# T14_V2_METROKNOME.net
KiCad netlist of a schematic drawn in EAGLE
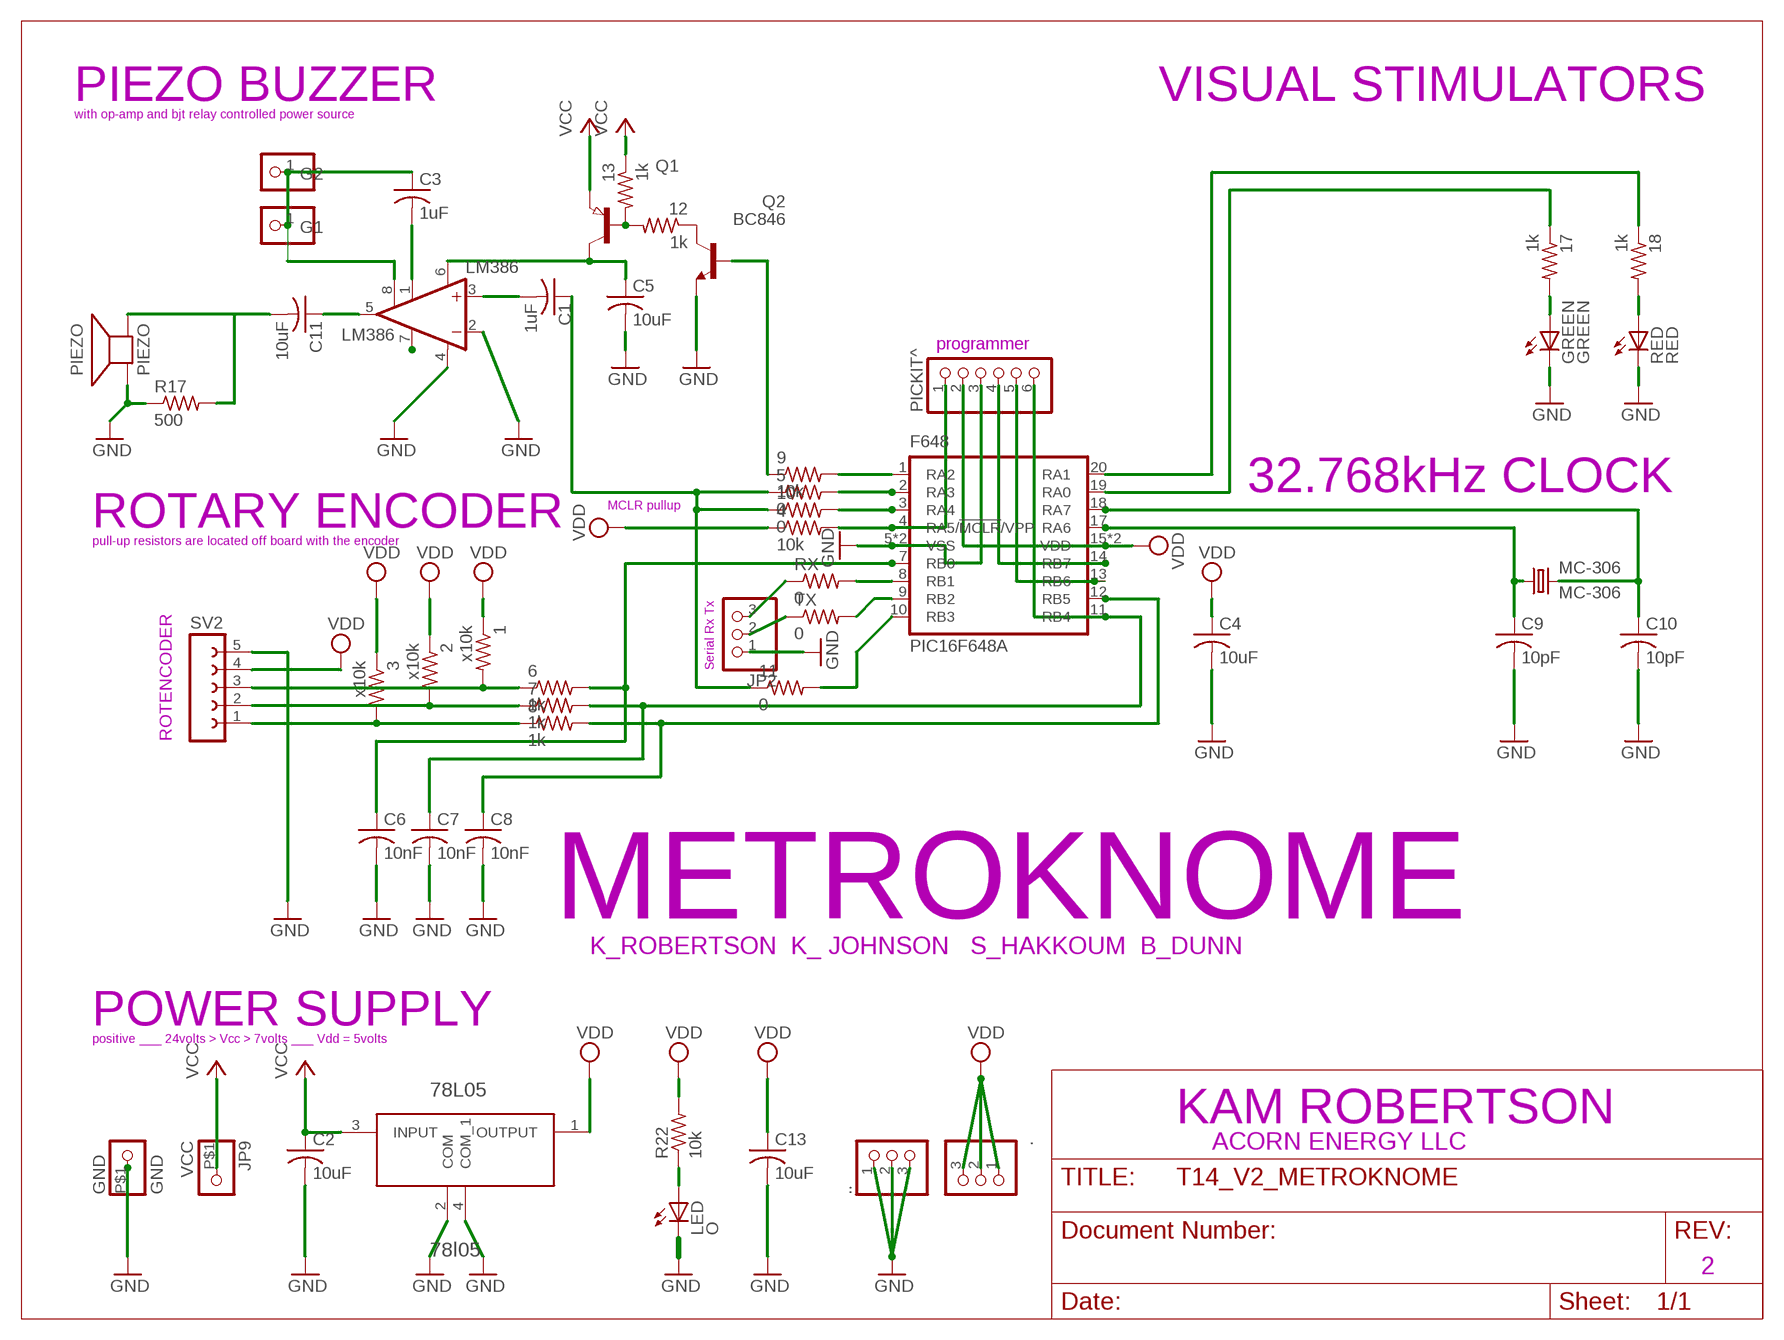
[diagram p0: schematic, sheet 1]

(export (version "E")
  (design (tool "Eeschema 10.0.6"))
  (components
    (comp (ref ".")
      (value "PINHD-1X3CB")
      (footprint "eagle-import:1X03-CLEANBIG")
      (libsource (lib "eagle-import") (part "PINHD-1X3CB"))
    )
    (comp (ref "..")
      (value "PINHD-1X3CB")
      (footprint "eagle-import:1X03-CLEANBIG")
      (libsource (lib "eagle-import") (part "PINHD-1X3CB"))
    )
    (comp (ref "1")
      (value "x10k")
      (footprint "eagle-import:R0603")
      (libsource (lib "eagle-import") (part "R-US_R0603"))
    )
    (comp (ref "2")
      (value "x10k")
      (footprint "eagle-import:R0603")
      (libsource (lib "eagle-import") (part "R-US_R0603"))
    )
    (comp (ref "3")
      (value "x10k")
      (footprint "eagle-import:R0603")
      (libsource (lib "eagle-import") (part "R-US_R0603"))
    )
    (comp (ref "4")
      (value "10k")
      (footprint "eagle-import:R1206")
      (libsource (lib "eagle-import") (part "R-US_R1206"))
    )
    (comp (ref "5")
      (value "0")
      (footprint "eagle-import:R0603")
      (libsource (lib "eagle-import") (part "R-US_R0603"))
    )
    (comp (ref "6")
      (value "1k")
      (footprint "eagle-import:R1206")
      (libsource (lib "eagle-import") (part "R-US_R1206"))
    )
    (comp (ref "7")
      (value "1k")
      (footprint "eagle-import:R1206")
      (libsource (lib "eagle-import") (part "R-US_R1206"))
    )
    (comp (ref "8")
      (value "1k")
      (footprint "eagle-import:R1206")
      (libsource (lib "eagle-import") (part "R-US_R1206"))
    )
    (comp (ref "9")
      (value "10k")
      (footprint "eagle-import:R1206")
      (libsource (lib "eagle-import") (part "R-US_R1206"))
    )
    (comp (ref "10")
      (value "0")
      (footprint "eagle-import:R0603")
      (libsource (lib "eagle-import") (part "R-US_R0603"))
    )
    (comp (ref "11")
      (value "0")
      (footprint "eagle-import:R1206")
      (libsource (lib "eagle-import") (part "R-US_R1206"))
    )
    (comp (ref "12")
      (value "1k")
      (footprint "eagle-import:R1206")
      (libsource (lib "eagle-import") (part "R-US_R1206"))
    )
    (comp (ref "13")
      (value "1k")
      (footprint "eagle-import:R1206")
      (libsource (lib "eagle-import") (part "R-US_R1206"))
    )
    (comp (ref "17")
      (value "1k")
      (footprint "eagle-import:R1206")
      (libsource (lib "eagle-import") (part "R-US_R1206"))
    )
    (comp (ref "18")
      (value "1k")
      (footprint "eagle-import:R1206")
      (libsource (lib "eagle-import") (part "R-US_R1206"))
    )
    (comp (ref "78L05")
      (value "78l05")
      (footprint "eagle-import:SOT150P400X160-4N")
      (fields (field (name "MPN") "UA78L05ACPKG3"))
      (libsource (lib "eagle-import") (part "UA78L05ACPKG3"))
    )
    (comp (ref "C1")
      (value "1uF")
      (footprint "eagle-import:C1210")
      (libsource (lib "eagle-import") (part "C-USC1210"))
    )
    (comp (ref "C2")
      (value "10uF")
      (footprint "eagle-import:C1210")
      (libsource (lib "eagle-import") (part "C-USC1210"))
    )
    (comp (ref "C3")
      (value "1uF")
      (footprint "eagle-import:C1210")
      (libsource (lib "eagle-import") (part "C-USC1210"))
    )
    (comp (ref "C4")
      (value "10uF")
      (footprint "eagle-import:C1210")
      (libsource (lib "eagle-import") (part "C-USC1210"))
    )
    (comp (ref "C5")
      (value "10uF")
      (footprint "eagle-import:C1210")
      (libsource (lib "eagle-import") (part "C-USC1210"))
    )
    (comp (ref "C6")
      (value "10nF")
      (footprint "eagle-import:C1210")
      (libsource (lib "eagle-import") (part "C-USC1210"))
    )
    (comp (ref "C7")
      (value "10nF")
      (footprint "eagle-import:C1210")
      (libsource (lib "eagle-import") (part "C-USC1210"))
    )
    (comp (ref "C8")
      (value "10nF")
      (footprint "eagle-import:C1210")
      (libsource (lib "eagle-import") (part "C-USC1210"))
    )
    (comp (ref "C9")
      (value "10pF")
      (footprint "eagle-import:C1210")
      (libsource (lib "eagle-import") (part "C-USC1210"))
    )
    (comp (ref "C10")
      (value "10pF")
      (footprint "eagle-import:C1210")
      (libsource (lib "eagle-import") (part "C-USC1210"))
    )
    (comp (ref "C11")
      (value "10uF")
      (footprint "eagle-import:C1210")
      (libsource (lib "eagle-import") (part "C-USC1210"))
    )
    (comp (ref "C13")
      (value "10uF")
      (footprint "eagle-import:C1210")
      (libsource (lib "eagle-import") (part "C-USC1210"))
    )
    (comp (ref "F648")
      (value "PIC16F648A")
      (footprint "eagle-import:SSOP20")
      (libsource (lib "eagle-import") (part "PIC16F1826/27SS"))
    )
    (comp (ref "G1")
      (value "PINHD-1X1CB")
      (footprint "eagle-import:1X01-CLEANBIG")
      (libsource (lib "eagle-import") (part "PINHD-1X1CB"))
    )
    (comp (ref "G2")
      (value "PINHD-1X1CB")
      (footprint "eagle-import:1X01-CLEANBIG")
      (libsource (lib "eagle-import") (part "PINHD-1X1CB"))
    )
    (comp (ref "GND")
      (value "GND")
      (footprint "eagle-import:1X1-BIGPOGO")
      (libsource (lib "eagle-import") (part "PINHD-1X1-BIGPOGO"))
    )
    (comp (ref "GREEN")
      (value "GREEN")
      (footprint "eagle-import:LED5MM")
      (libsource (lib "eagle-import") (part "LED5MM"))
    )
    (comp (ref "JP2")
      (value "PINHD-1X3CB")
      (footprint "eagle-import:1X03-CLEANBIG")
      (libsource (lib "eagle-import") (part "PINHD-1X3CB"))
    )
    (comp (ref "JP9")
      (value "VCC")
      (footprint "eagle-import:1X1-BIGPOGO")
      (libsource (lib "eagle-import") (part "PINHD-1X1-BIGPOGO"))
    )
    (comp (ref "LED")
      (value "O")
      (footprint "eagle-import:CHIPLED_1206")
      (libsource (lib "eagle-import") (part "LEDCHIPLED_1206"))
    )
    (comp (ref "LM386")
      (value "LM386")
      (footprint "eagle-import:SO08")
      (libsource (lib "eagle-import") (part "LM386?-M1"))
    )
    (comp (ref "MC-306")
      (value "MC-306")
      (footprint "eagle-import:MC-306")
      (fields
        (field (name "MPN") "MC-306 60.0KHZ  100PPM ,12.5PF")
        (field (name "MPN_1") "MC-306 60.0KHZ  100PPM ,12.5PF")
        (field (name "OC_FARNELL") "1278040")
        (field (name "OC_NEWARK") "31M5576")
      )
      (libsource (lib "eagle-import") (part "MC-306"))
    )
    (comp (ref "PICKIT^")
      (value "PINHD-1X6LOCK")
      (footprint "eagle-import:1X06-BIGLOCK")
      (libsource (lib "eagle-import") (part "PINHD-1X6LOCK"))
    )
    (comp (ref "PIEZO")
      (value "PIEZO")
      (footprint "eagle-import:PS12")
      (libsource (lib "eagle-import") (part "SPEAKER/PS12"))
    )
    (comp (ref "Q1")
      (value "PNP-TRANSISTOR_SOT89")
      (footprint "eagle-import:SOT89")
      (libsource (lib "eagle-import") (part "PNP-TRANSISTOR_SOT89"))
    )
    (comp (ref "Q2")
      (value "BC846")
      (footprint "eagle-import:SOT23")
      (libsource (lib "eagle-import") (part "BC846"))
    )
    (comp (ref "R17")
      (value "500")
      (footprint "eagle-import:R1206")
      (libsource (lib "eagle-import") (part "R-US_R1206"))
    )
    (comp (ref "R22")
      (value "10k")
      (footprint "eagle-import:R1206")
      (libsource (lib "eagle-import") (part "R-US_R1206"))
    )
    (comp (ref "RED")
      (value "RED")
      (footprint "eagle-import:LED5MM")
      (libsource (lib "eagle-import") (part "LED5MM"))
    )
    (comp (ref "RX")
      (value "0")
      (footprint "eagle-import:R1206")
      (libsource (lib "eagle-import") (part "R-US_R1206"))
    )
    (comp (ref "SV2")
      (value "FE05-1")
      (footprint "eagle-import:FE05-1")
      (libsource (lib "eagle-import") (part "FE05-1"))
    )
    (comp (ref "TX")
      (value "0")
      (footprint "eagle-import:R1206")
      (libsource (lib "eagle-import") (part "R-US_R1206"))
    )
  )
  (nets
    (net (code "1") (name "GND") (class "Default")
      (node (ref "..") (pin "1") (pinfunction "1_1") (pintype "passive"))
      (node (ref "..") (pin "2") (pinfunction "2_2") (pintype "passive"))
      (node (ref "..") (pin "3") (pinfunction "3_3") (pintype "passive"))
      (node (ref "78L05") (pin "2") (pinfunction "COM_2") (pintype "power_in"))
      (node (ref "78L05") (pin "4") (pinfunction "COM_1_4") (pintype "power_in"))
      (node (ref "C10") (pin "2") (pinfunction "2_2") (pintype "passive"))
      (node (ref "C13") (pin "2") (pinfunction "2_2") (pintype "passive"))
      (node (ref "C2") (pin "2") (pinfunction "2_2") (pintype "passive"))
      (node (ref "C4") (pin "2") (pinfunction "2_2") (pintype "passive"))
      (node (ref "C5") (pin "2") (pinfunction "2_2") (pintype "passive"))
      (node (ref "C6") (pin "2") (pinfunction "2_2") (pintype "passive"))
      (node (ref "C7") (pin "2") (pinfunction "2_2") (pintype "passive"))
      (node (ref "C8") (pin "2") (pinfunction "2_2") (pintype "passive"))
      (node (ref "C9") (pin "2") (pinfunction "2_2") (pintype "passive"))
      (node (ref "F648") (pin "5") (pinfunction "VSS_5") (pintype "power_in"))
      (node (ref "F648") (pin "6") (pinfunction "VSS_6") (pintype "power_in"))
      (node (ref "GND") (pin "P$1") (pinfunction "1_P$1") (pintype "passive"))
      (node (ref "GREEN") (pin "K") (pinfunction "C_K") (pintype "passive"))
      (node (ref "JP2") (pin "1") (pinfunction "1_1") (pintype "passive"))
      (node (ref "LED") (pin "C") (pinfunction "C_C") (pintype "passive"))
      (node (ref "LM386") (pin "2") (pinfunction "-IN_2") (pintype "input"))
      (node (ref "LM386") (pin "4") (pinfunction "GND_4") (pintype "power_in"))
      (node (ref "PICKIT^") (pin "3") (pinfunction "3_3") (pintype "passive"))
      (node (ref "PIEZO") (pin "P$2") (pinfunction "-_P$2") (pintype "passive"))
      (node (ref "Q2") (pin "2") (pinfunction "E_2") (pintype "passive"))
      (node (ref "R17") (pin "1") (pinfunction "1_1") (pintype "passive"))
      (node (ref "RED") (pin "K") (pinfunction "C_K") (pintype "passive"))
      (node (ref "SV2") (pin "5") (pinfunction "5_5") (pintype "passive"))
    )
    (net (code "2") (name "Net-(1-Pad2)") (class "Default")
      (node (ref "1") (pin "2") (pinfunction "2_2") (pintype "passive"))
      (node (ref "6") (pin "1") (pinfunction "1_1") (pintype "passive"))
      (node (ref "SV2") (pin "3") (pinfunction "3_3") (pintype "passive"))
    )
    (net (code "3") (name "Net-(2-Pad2)") (class "Default")
      (node (ref "2") (pin "2") (pinfunction "2_2") (pintype "passive"))
      (node (ref "7") (pin "1") (pinfunction "1_1") (pintype "passive"))
      (node (ref "SV2") (pin "2") (pinfunction "2_2") (pintype "passive"))
    )
    (net (code "4") (name "Net-(3-Pad2)") (class "Default")
      (node (ref "3") (pin "2") (pinfunction "2_2") (pintype "passive"))
      (node (ref "8") (pin "1") (pinfunction "1_1") (pintype "passive"))
      (node (ref "SV2") (pin "1") (pinfunction "1_1") (pintype "passive"))
    )
    (net (code "5") (name "Net-(10-Pad1)") (class "Default")
      (node (ref "10") (pin "1") (pinfunction "1_1") (pintype "passive"))
      (node (ref "11") (pin "1") (pinfunction "1_1") (pintype "passive"))
      (node (ref "5") (pin "1") (pinfunction "1_1") (pintype "passive"))
      (node (ref "C1") (pin "1") (pinfunction "1_1") (pintype "passive"))
    )
    (net (code "6") (name "Net-(17-Pad2)") (class "Default")
      (node (ref "17") (pin "2") (pinfunction "2_2") (pintype "passive"))
      (node (ref "GREEN") (pin "A") (pinfunction "A_A") (pintype "passive"))
    )
    (net (code "7") (name "Net-(18-Pad2)") (class "Default")
      (node (ref "18") (pin "2") (pinfunction "2_2") (pintype "passive"))
      (node (ref "RED") (pin "A") (pinfunction "A_A") (pintype "passive"))
    )
    (net (code "8") (name "Net-(C3-Pad1)") (class "Default")
      (node (ref "C3") (pin "1") (pinfunction "1_1") (pintype "passive"))
      (node (ref "G1") (pin "1") (pinfunction "1_1") (pintype "passive"))
      (node (ref "G2") (pin "1") (pinfunction "1_1") (pintype "passive"))
      (node (ref "LM386") (pin "8") (pinfunction "GAIN_8") (pintype "passive"))
    )
    (net (code "9") (name "Net-(C3-Pad2)") (class "Default")
      (node (ref "C3") (pin "2") (pinfunction "2_2") (pintype "passive"))
      (node (ref "LM386") (pin "1") (pinfunction "GAIN_1") (pintype "passive"))
    )
    (net (code "10") (name "Net-(F648-RA0)") (class "Default")
      (node (ref "17") (pin "1") (pinfunction "1_1") (pintype "passive"))
      (node (ref "F648") (pin "19") (pinfunction "RA0_19") (pintype "bidirectional"))
    )
    (net (code "11") (name "Net-(F648-RA1)") (class "Default")
      (node (ref "18") (pin "1") (pinfunction "1_1") (pintype "passive"))
      (node (ref "F648") (pin "20") (pinfunction "RA1_20") (pintype "bidirectional"))
    )
    (net (code "12") (name "Net-(F648-RA2)") (class "Default")
      (node (ref "9") (pin "2") (pinfunction "2_2") (pintype "passive"))
      (node (ref "F648") (pin "1") (pinfunction "RA2_1") (pintype "bidirectional"))
    )
    (net (code "13") (name "Net-(F648-RA3)") (class "Default")
      (node (ref "5") (pin "2") (pinfunction "2_2") (pintype "passive"))
      (node (ref "F648") (pin "2") (pinfunction "RA3_2") (pintype "bidirectional"))
    )
    (net (code "14") (name "Net-(F648-RA4)") (class "Default")
      (node (ref "10") (pin "2") (pinfunction "2_2") (pintype "passive"))
      (node (ref "F648") (pin "3") (pinfunction "RA4_3") (pintype "bidirectional"))
    )
    (net (code "15") (name "Net-(F648-RA5{slash}~{MCLR}{slash}VPP)") (class "Default")
      (node (ref "4") (pin "2") (pinfunction "2_2") (pintype "passive"))
      (node (ref "F648") (pin "4") (pinfunction "RA5/~{MCLR}/VPP_4") (pintype "bidirectional"))
      (node (ref "PICKIT^") (pin "1") (pinfunction "1_1") (pintype "passive"))
    )
    (net (code "16") (name "Net-(F648-RA6)") (class "Default")
      (node (ref "C9") (pin "1") (pinfunction "1_1") (pintype "passive"))
      (node (ref "F648") (pin "17") (pinfunction "RA6_17") (pintype "bidirectional"))
      (node (ref "MC-306") (pin "1") (pinfunction "1_1") (pintype "passive"))
    )
    (net (code "17") (name "Net-(F648-RA7)") (class "Default")
      (node (ref "C10") (pin "1") (pinfunction "1_1") (pintype "passive"))
      (node (ref "F648") (pin "18") (pinfunction "RA7_18") (pintype "bidirectional"))
      (node (ref "MC-306") (pin "4") (pinfunction "2_4") (pintype "passive"))
    )
    (net (code "18") (name "Net-(F648-RB0)") (class "Default")
      (node (ref "6") (pin "2") (pinfunction "2_2") (pintype "passive"))
      (node (ref "C6") (pin "1") (pinfunction "1_1") (pintype "passive"))
      (node (ref "F648") (pin "7") (pinfunction "RB0_7") (pintype "bidirectional"))
    )
    (net (code "19") (name "Net-(F648-RB1)") (class "Default")
      (node (ref "F648") (pin "8") (pinfunction "RB1_8") (pintype "bidirectional"))
      (node (ref "RX") (pin "2") (pinfunction "2_2") (pintype "passive"))
    )
    (net (code "20") (name "Net-(F648-RB2)") (class "Default")
      (node (ref "F648") (pin "9") (pinfunction "RB2_9") (pintype "bidirectional"))
      (node (ref "TX") (pin "2") (pinfunction "2_2") (pintype "passive"))
    )
    (net (code "21") (name "Net-(F648-RB3)") (class "Default")
      (node (ref "11") (pin "2") (pinfunction "2_2") (pintype "passive"))
      (node (ref "F648") (pin "10") (pinfunction "RB3_10") (pintype "bidirectional"))
    )
    (net (code "22") (name "Net-(F648-RB4)") (class "Default")
      (node (ref "7") (pin "2") (pinfunction "2_2") (pintype "passive"))
      (node (ref "C7") (pin "1") (pinfunction "1_1") (pintype "passive"))
      (node (ref "F648") (pin "11") (pinfunction "RB4_11") (pintype "bidirectional"))
      (node (ref "PICKIT^") (pin "6") (pinfunction "6_6") (pintype "passive"))
    )
    (net (code "23") (name "Net-(F648-RB5)") (class "Default")
      (node (ref "8") (pin "2") (pinfunction "2_2") (pintype "passive"))
      (node (ref "C8") (pin "1") (pinfunction "1_1") (pintype "passive"))
      (node (ref "F648") (pin "12") (pinfunction "RB5_12") (pintype "bidirectional"))
    )
    (net (code "24") (name "Net-(F648-RB6)") (class "Default")
      (node (ref "F648") (pin "13") (pinfunction "RB6_13") (pintype "bidirectional"))
      (node (ref "PICKIT^") (pin "5") (pinfunction "5_5") (pintype "passive"))
    )
    (net (code "25") (name "Net-(F648-RB7)") (class "Default")
      (node (ref "F648") (pin "14") (pinfunction "RB7_14") (pintype "bidirectional"))
      (node (ref "PICKIT^") (pin "4") (pinfunction "4_4") (pintype "passive"))
    )
    (net (code "26") (name "Net-(JP2-Pad2)") (class "Default")
      (node (ref "JP2") (pin "2") (pinfunction "2_2") (pintype "passive"))
      (node (ref "TX") (pin "1") (pinfunction "1_1") (pintype "passive"))
    )
    (net (code "27") (name "Net-(JP2-Pad3)") (class "Default")
      (node (ref "JP2") (pin "3") (pinfunction "3_3") (pintype "passive"))
      (node (ref "RX") (pin "1") (pinfunction "1_1") (pintype "passive"))
    )
    (net (code "28") (name "Net-(LED-PadA)") (class "Default")
      (node (ref "LED") (pin "A") (pinfunction "A_A") (pintype "passive"))
      (node (ref "R22") (pin "1") (pinfunction "1_1") (pintype "passive"))
    )
    (net (code "29") (name "Net-(LM386-+IN)") (class "Default")
      (node (ref "C1") (pin "2") (pinfunction "2_2") (pintype "passive"))
      (node (ref "LM386") (pin "3") (pinfunction "+IN_3") (pintype "input"))
    )
    (net (code "30") (name "Net-(LM386-OUT)") (class "Default")
      (node (ref "C11") (pin "1") (pinfunction "1_1") (pintype "passive"))
      (node (ref "LM386") (pin "5") (pinfunction "OUT_5") (pintype "output"))
    )
    (net (code "31") (name "Net-(LM386-VS)") (class "Default")
      (node (ref "C5") (pin "1") (pinfunction "1_1") (pintype "passive"))
      (node (ref "LM386") (pin "6") (pinfunction "VS_6") (pintype "power_in"))
      (node (ref "Q1") (pin "2") (pinfunction "C_2") (pintype "passive"))
    )
    (net (code "32") (name "Net-(PIEZO-+)") (class "Default")
      (node (ref "C11") (pin "2") (pinfunction "2_2") (pintype "passive"))
      (node (ref "PIEZO") (pin "P$1") (pinfunction "+_P$1") (pintype "passive"))
      (node (ref "R17") (pin "2") (pinfunction "2_2") (pintype "passive"))
    )
    (net (code "33") (name "Net-(Q1-B)") (class "Default")
      (node (ref "12") (pin "2") (pinfunction "2_2") (pintype "passive"))
      (node (ref "13") (pin "2") (pinfunction "2_2") (pintype "passive"))
      (node (ref "Q1") (pin "1") (pinfunction "B_1") (pintype "passive"))
    )
    (net (code "34") (name "Net-(Q2-B)") (class "Default")
      (node (ref "9") (pin "1") (pinfunction "1_1") (pintype "passive"))
      (node (ref "Q2") (pin "1") (pinfunction "B_1") (pintype "passive"))
    )
    (net (code "35") (name "Net-(Q2-C)") (class "Default")
      (node (ref "12") (pin "1") (pinfunction "1_1") (pintype "passive"))
      (node (ref "Q2") (pin "3") (pinfunction "C_3") (pintype "passive"))
    )
    (net (code "36") (name "VCC") (class "Default")
      (node (ref "13") (pin "1") (pinfunction "1_1") (pintype "passive"))
      (node (ref "78L05") (pin "3") (pinfunction "INPUT_3") (pintype "input"))
      (node (ref "C2") (pin "1") (pinfunction "1_1") (pintype "passive"))
      (node (ref "JP9") (pin "P$1") (pinfunction "1_P$1") (pintype "passive"))
      (node (ref "Q1") (pin "3") (pinfunction "E_3") (pintype "passive"))
    )
    (net (code "37") (name "VDD") (class "Default")
      (node (ref ".") (pin "1") (pinfunction "1_1") (pintype "passive"))
      (node (ref ".") (pin "2") (pinfunction "2_2") (pintype "passive"))
      (node (ref ".") (pin "3") (pinfunction "3_3") (pintype "passive"))
      (node (ref "1") (pin "1") (pinfunction "1_1") (pintype "passive"))
      (node (ref "2") (pin "1") (pinfunction "1_1") (pintype "passive"))
      (node (ref "3") (pin "1") (pinfunction "1_1") (pintype "passive"))
      (node (ref "4") (pin "1") (pinfunction "1_1") (pintype "passive"))
      (node (ref "78L05") (pin "1") (pinfunction "OUTPUT_1") (pintype "output"))
      (node (ref "C13") (pin "1") (pinfunction "1_1") (pintype "passive"))
      (node (ref "C4") (pin "1") (pinfunction "1_1") (pintype "passive"))
      (node (ref "F648") (pin "15") (pinfunction "VDD_15") (pintype "power_in"))
      (node (ref "F648") (pin "16") (pinfunction "VDD_16") (pintype "power_in"))
      (node (ref "PICKIT^") (pin "2") (pinfunction "2_2") (pintype "passive"))
      (node (ref "R22") (pin "2") (pinfunction "2_2") (pintype "passive"))
      (node (ref "SV2") (pin "4") (pinfunction "4_4") (pintype "passive"))
    )
    (net (code "38") (name "unconnected-(LM386-BYPASS-Pad7)") (class "Default")
      (node (ref "LM386") (pin "7") (pinfunction "BYPASS_7") (pintype "passive"))
    )
  )
)
